# IsoDiffProbe.net
KiCad netlist of a schematic drawn in Altium Designer
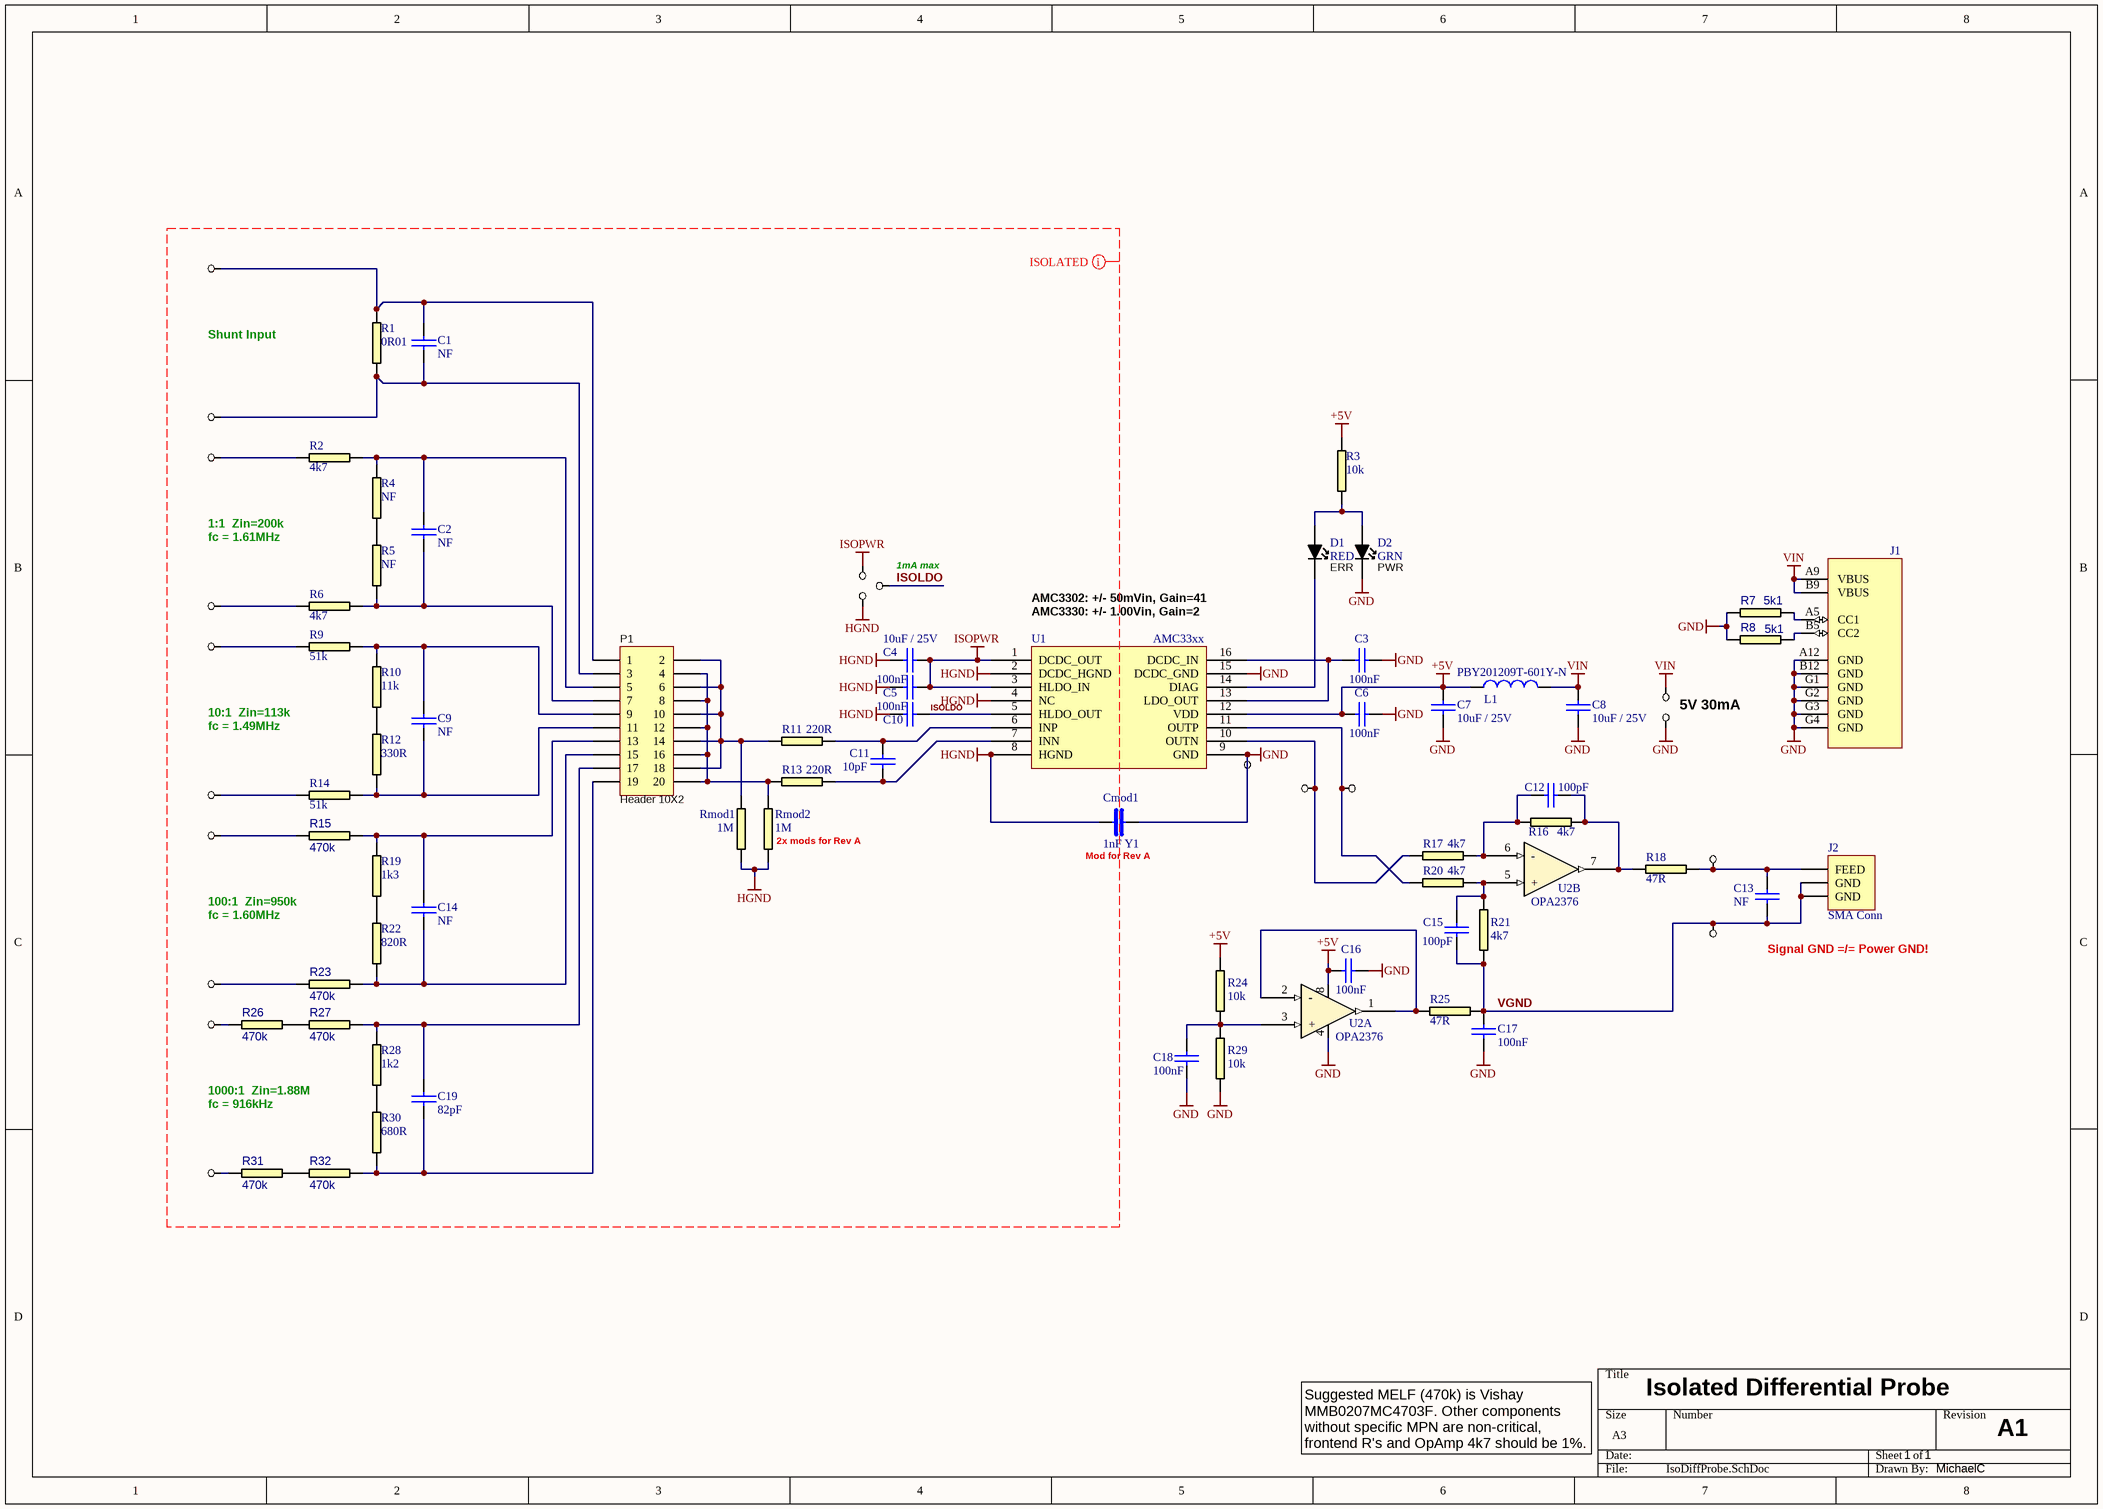
[diagram p0: IsoDiffProbe.SchDoc]

(export (version "E")
  (design (tool "Eeschema 10.0.6"))
  (components
    (comp (ref "C1")
      (value "NF")
      (footprint "NixieClock_RevA:0603")
      (description "Capacitor - S/M")
      (libsource (lib "altium-import") (part "root_0_CAP-STD-SM_"))
    )
    (comp (ref "C2")
      (value "NF")
      (footprint "NixieClock_RevA:0603")
      (description "Capacitor - S/M")
      (libsource (lib "altium-import") (part "root_0_CAP-STD-SM_"))
    )
    (comp (ref "C3")
      (value "100nF")
      (footprint "NixieClock_RevA:0603")
      (description "Capacitor - S/M")
      (libsource (lib "altium-import") (part "root_1_mirrored_CAP-STD-SM_"))
    )
    (comp (ref "C4")
      (value "10uF / 25V")
      (footprint "0805_cap_Rounded")
      (description "Capacitor - S/M")
      (libsource (lib "altium-import") (part "root_1_CAP-STD-SM_"))
    )
    (comp (ref "C5")
      (value "100nF")
      (footprint "NixieClock_RevA:0603")
      (description "Capacitor - S/M")
      (libsource (lib "altium-import") (part "root_1_mirrored_CAP-STD-SM_"))
    )
    (comp (ref "C6")
      (value "100nF")
      (footprint "NixieClock_RevA:0603")
      (description "Capacitor - S/M")
      (libsource (lib "altium-import") (part "root_1_mirrored_CAP-STD-SM_"))
    )
    (comp (ref "C7")
      (value "10uF / 25V")
      (footprint "0805_cap_Rounded")
      (description "Capacitor - S/M")
      (libsource (lib "altium-import") (part "root_0_CAP-STD-SM_"))
    )
    (comp (ref "C8")
      (value "10uF / 25V")
      (footprint "0805_cap_Rounded")
      (description "Capacitor - S/M")
      (libsource (lib "altium-import") (part "root_0_CAP-STD-SM_"))
    )
    (comp (ref "C9")
      (value "NF")
      (footprint "NixieClock_RevA:0603")
      (description "Capacitor - S/M")
      (libsource (lib "altium-import") (part "root_0_CAP-STD-SM_"))
    )
    (comp (ref "C10")
      (value "100nF")
      (footprint "NixieClock_RevA:0603")
      (description "Capacitor - S/M")
      (libsource (lib "altium-import") (part "root_1_mirrored_CAP-STD-SM_"))
    )
    (comp (ref "C11")
      (value "10pF")
      (footprint "NixieClock_RevA:0603")
      (description "Capacitor - S/M")
      (libsource (lib "altium-import") (part "root_0_mirrored_CAP-STD-SM_"))
    )
    (comp (ref "C12")
      (value "100pF")
      (footprint "NixieClock_RevA:0603")
      (description "Capacitor - S/M")
      (libsource (lib "altium-import") (part "root_3_mirrored_CAP-STD-SM_"))
    )
    (comp (ref "C13")
      (value "NF")
      (footprint "NixieClock_RevA:0603")
      (description "Capacitor - S/M")
      (libsource (lib "altium-import") (part "root_0_mirrored_CAP-STD-SM_"))
    )
    (comp (ref "C14")
      (value "NF")
      (footprint "NixieClock_RevA:0603")
      (description "Capacitor - S/M")
      (libsource (lib "altium-import") (part "root_0_CAP-STD-SM_"))
    )
    (comp (ref "C15")
      (value "100pF")
      (footprint "NixieClock_RevA:0603")
      (description "Capacitor - S/M")
      (libsource (lib "altium-import") (part "root_0_mirrored_CAP-STD-SM_"))
    )
    (comp (ref "C16")
      (value "100nF")
      (footprint "NixieClock_RevA:0603")
      (description "Capacitor - S/M")
      (libsource (lib "altium-import") (part "root_3_mirrored_CAP-STD-SM_"))
    )
    (comp (ref "C17")
      (value "100nF")
      (footprint "NixieClock_RevA:0603")
      (description "Capacitor - S/M")
      (libsource (lib "altium-import") (part "root_0_mirrored_CAP-STD-SM_"))
    )
    (comp (ref "C18")
      (value "100nF")
      (footprint "NixieClock_RevA:0603")
      (description "Capacitor - S/M")
      (libsource (lib "altium-import") (part "root_0_mirrored_CAP-STD-SM_"))
    )
    (comp (ref "C19")
      (value "82pF")
      (footprint "NixieClock_RevA:0603")
      (description "Capacitor - S/M")
      (libsource (lib "altium-import") (part "root_0_CAP-STD-SM_"))
    )
    (comp (ref "Cmod1")
      (value "1nF Y1")
      (footprint "RAD0.4Y1")
      (description "Capacitor - Through Hole")
      (libsource (lib "E") (part "CAP-STD-TH"))
    )
    (comp (ref "D1") (value "RED") (footprint "LED-0603") (libsource (lib "NixieClock_RevA") (part "LED")))
    (comp (ref "D2") (value "GRN") (footprint "LED-0603") (libsource (lib "NixieClock_RevA") (part "LED")))
    (comp (ref "J1")
      (value "USB C 6-Pin")
      (footprint "USB-C_6pin_Conn")
      (description "USB Type C Receptacle Power Only (6 pin)")
      (libsource (lib "NixieClock_RevA") (part "USB-C_6pin"))
    )
    (comp (ref "J2")
      (value "SMA Conn")
      (footprint "SMA_SMD")
      (description "SMA connector, mid-mount")
      (libsource (lib "NixieClock_RevA") (part "SMA_SMD"))
    )
    (comp (ref "L1")
      (value "PBY201209T-601Y-N")
      (footprint "0805_Rounded")
      (description "Ferrite Bead WE-CBF, Z = 600 Ohm")
      (libsource (lib "DataloggingClock") (part "PBY201209T-601Y-N"))
    )
    (comp (ref "P1")
      (value "Header 10X2")
      (footprint "IDC20")
      (description "Header, 10-Pin, Dual row")
      (libsource (lib "E") (part "Header 10X2"))
    )
    (comp (ref "R1")
      (value "0R01")
      (footprint "NixieClock_RevA:1206")
      (description "Resistor - S/M")
      (libsource (lib "") (part "RES-SM_2"))
    )
    (comp (ref "R2")
      (value "4k7")
      (footprint "NixieClock_RevA:1206")
      (description "Resistor - S/M")
      (libsource (lib "") (part "RES-SM_3"))
    )
    (comp (ref "R3")
      (value "10k")
      (footprint "NixieClock_RevA:0603")
      (description "Resistor - S/M")
      (libsource (lib "") (part "RES-SM_2"))
    )
    (comp (ref "R4")
      (value "NF")
      (footprint "NixieClock_RevA:0603")
      (description "Resistor - S/M")
      (libsource (lib "") (part "RES-SM_1"))
    )
    (comp (ref "R5")
      (value "NF")
      (footprint "NixieClock_RevA:0603")
      (description "Resistor - S/M")
      (libsource (lib "") (part "RES-SM_1"))
    )
    (comp (ref "R6")
      (value "4k7")
      (footprint "NixieClock_RevA:1206")
      (description "Resistor - S/M")
      (libsource (lib "") (part "RES-SM_3"))
    )
    (comp (ref "R7")
      (value "5k1")
      (footprint "NixieClock_RevA:0603")
      (description "Resistor SMD")
      (libsource (lib "Genesis_SCH_Symbols") (part "ResSMD"))
    )
    (comp (ref "R8")
      (value "5k1")
      (footprint "NixieClock_RevA:0603")
      (description "Resistor SMD")
      (libsource (lib "Genesis_SCH_Symbols") (part "ResSMD"))
    )
    (comp (ref "R9")
      (value "51k")
      (footprint "NixieClock_RevA:1206")
      (description "Resistor - S/M")
      (libsource (lib "") (part "RES-SM_3"))
    )
    (comp (ref "R10")
      (value "11k")
      (footprint "NixieClock_RevA:0603")
      (description "Resistor - S/M")
      (libsource (lib "") (part "RES-SM_1"))
    )
    (comp (ref "R11")
      (value "220R")
      (footprint "NixieClock_RevA:0603")
      (description "Resistor - S/M")
      (libsource (lib "NixieClock_RevA") (part "RES-SM"))
    )
    (comp (ref "R12")
      (value "330R")
      (footprint "NixieClock_RevA:0603")
      (description "Resistor - S/M")
      (libsource (lib "") (part "RES-SM_1"))
    )
    (comp (ref "R13")
      (value "220R")
      (footprint "NixieClock_RevA:0603")
      (description "Resistor - S/M")
      (libsource (lib "NixieClock_RevA") (part "RES-SM"))
    )
    (comp (ref "R14")
      (value "51k")
      (footprint "NixieClock_RevA:1206")
      (description "Resistor - S/M")
      (libsource (lib "") (part "RES-SM_3"))
    )
    (comp (ref "R15")
      (value "470k")
      (footprint "E General:MMB0207")
      (description "Resistor SMD")
      (libsource (lib "NixieClock_RevA") (part "ResSMD"))
    )
    (comp (ref "R16")
      (value "4k7")
      (footprint "NixieClock_RevA:0603")
      (description "Resistor - S/M")
      (libsource (lib "") (part "RES-SM_3"))
    )
    (comp (ref "R17")
      (value "4k7")
      (footprint "NixieClock_RevA:0603")
      (description "Resistor - S/M")
      (libsource (lib "NixieClock_RevA") (part "RES-SM"))
    )
    (comp (ref "R18")
      (value "47R")
      (footprint "NixieClock_RevA:0603")
      (description "Resistor - S/M")
      (libsource (lib "NixieClock_RevA") (part "RES-SM"))
    )
    (comp (ref "R19")
      (value "1k3")
      (footprint "NixieClock_RevA:0603")
      (description "Resistor - S/M")
      (libsource (lib "") (part "RES-SM_1"))
    )
    (comp (ref "R20")
      (value "4k7")
      (footprint "NixieClock_RevA:0603")
      (description "Resistor - S/M")
      (libsource (lib "NixieClock_RevA") (part "RES-SM"))
    )
    (comp (ref "R21")
      (value "4k7")
      (footprint "NixieClock_RevA:0603")
      (description "Resistor - S/M")
      (libsource (lib "") (part "RES-SM_1"))
    )
    (comp (ref "R22")
      (value "820R")
      (footprint "NixieClock_RevA:0603")
      (description "Resistor - S/M")
      (libsource (lib "") (part "RES-SM_1"))
    )
    (comp (ref "R23")
      (value "470k")
      (footprint "E General:MMB0207")
      (description "Resistor SMD")
      (libsource (lib "NixieClock_RevA") (part "ResSMD"))
    )
    (comp (ref "R24")
      (value "10k")
      (footprint "NixieClock_RevA:0603")
      (description "Resistor - S/M")
      (libsource (lib "") (part "RES-SM_1"))
    )
    (comp (ref "R25")
      (value "47R")
      (footprint "NixieClock_RevA:0603")
      (description "Resistor - S/M")
      (libsource (lib "NixieClock_RevA") (part "RES-SM"))
    )
    (comp (ref "R26")
      (value "470k")
      (footprint "E General:MMB0207")
      (description "Resistor SMD")
      (libsource (lib "NixieClock_RevA") (part "ResSMD"))
    )
    (comp (ref "R27")
      (value "470k")
      (footprint "E General:MMB0207")
      (description "Resistor SMD")
      (libsource (lib "NixieClock_RevA") (part "ResSMD"))
    )
    (comp (ref "R28")
      (value "1k2")
      (footprint "NixieClock_RevA:0603")
      (description "Resistor - S/M")
      (libsource (lib "") (part "RES-SM_1"))
    )
    (comp (ref "R29")
      (value "10k")
      (footprint "NixieClock_RevA:0603")
      (description "Resistor - S/M")
      (libsource (lib "") (part "RES-SM_1"))
    )
    (comp (ref "R30")
      (value "680R")
      (footprint "NixieClock_RevA:0603")
      (description "Resistor - S/M")
      (libsource (lib "") (part "RES-SM_1"))
    )
    (comp (ref "R31")
      (value "470k")
      (footprint "E General:MMB0207")
      (description "Resistor SMD")
      (libsource (lib "NixieClock_RevA") (part "ResSMD"))
    )
    (comp (ref "R32")
      (value "470k")
      (footprint "E General:MMB0207")
      (description "Resistor SMD")
      (libsource (lib "NixieClock_RevA") (part "ResSMD"))
    )
    (comp (ref "Rmod1")
      (value "1M")
      (footprint "NixieClock_RevA:0603")
      (description "Resistor - S/M")
      (libsource (lib "") (part "RES-SM_1"))
    )
    (comp (ref "Rmod2")
      (value "1M")
      (footprint "NixieClock_RevA:0603")
      (description "Resistor - S/M")
      (libsource (lib "") (part "RES-SM_1"))
    )
    (comp (ref "TP1")
      (value "Test Point")
      (footprint "TP")
      (description "Pad for Test Point")
      (libsource (lib "E") (part "TP"))
    )
    (comp (ref "TP2")
      (value "Test Point")
      (footprint "TP")
      (description "Pad for Test Point")
      (libsource (lib "E") (part "TP"))
    )
    (comp (ref "TP3")
      (value "Test Point")
      (footprint "TP")
      (description "Pad for Test Point")
      (libsource (lib "E") (part "TP"))
    )
    (comp (ref "TP4")
      (value "Test Point")
      (footprint "TP")
      (description "Pad for Test Point")
      (libsource (lib "E") (part "TP"))
    )
    (comp (ref "TP5")
      (value "Test Point")
      (footprint "TP")
      (description "Pad for Test Point")
      (libsource (lib "E") (part "TP"))
    )
    (comp (ref "TP6")
      (value "Test Point")
      (footprint "TP")
      (description "Pad for Test Point")
      (libsource (lib "E") (part "TP"))
    )
    (comp (ref "TP7")
      (value "Test Point")
      (footprint "TP")
      (description "Pad for Test Point")
      (libsource (lib "E") (part "TP"))
    )
    (comp (ref "TP8")
      (value "Test Point")
      (footprint "TP")
      (description "Pad for Test Point")
      (libsource (lib "E") (part "TP"))
    )
    (comp (ref "TP9")
      (value "Test Point")
      (footprint "TP")
      (description "Pad for Test Point")
      (libsource (lib "E") (part "TP"))
    )
    (comp (ref "TP10")
      (value "Test Point")
      (footprint "TP")
      (description "Pad for Test Point")
      (libsource (lib "E") (part "TP"))
    )
    (comp (ref "TP11")
      (value "Test Point")
      (footprint "TP")
      (description "Pad for Test Point")
      (libsource (lib "E") (part "TP"))
    )
    (comp (ref "TP12")
      (value "Test Point")
      (footprint "TP")
      (description "Pad for Test Point")
      (libsource (lib "E") (part "TP"))
    )
    (comp (ref "TP13")
      (value "Test Point")
      (footprint "TP")
      (description "Pad for Test Point")
      (libsource (lib "E") (part "TP"))
    )
    (comp (ref "TP14")
      (value "Test Point")
      (footprint "TP")
      (description "Pad for Test Point")
      (libsource (lib "E") (part "TP"))
    )
    (comp (ref "TP15")
      (value "Test Point")
      (footprint "TP")
      (description "Pad for Test Point")
      (libsource (lib "E") (part "TP"))
    )
    (comp (ref "TP16")
      (value "Test Point")
      (footprint "TP")
      (description "Pad for Test Point")
      (libsource (lib "E") (part "TP"))
    )
    (comp (ref "TP17")
      (value "Test Point")
      (footprint "TP")
      (description "Pad for Test Point")
      (libsource (lib "E") (part "TP"))
    )
    (comp (ref "TP18")
      (value "Test Point")
      (footprint "TP")
      (description "Pad for Test Point")
      (libsource (lib "E") (part "TP"))
    )
    (comp (ref "TP19")
      (value "Test Point")
      (footprint "TP")
      (description "Pad for Test Point")
      (libsource (lib "E") (part "TP"))
    )
    (comp (ref "TP20")
      (value "Test Point")
      (footprint "TP")
      (description "Pad for Test Point")
      (libsource (lib "E") (part "TP"))
    )
    (comp (ref "U1")
      (value "AMC33xx")
      (footprint "DW0016B")
      (description "Isolated differential analog sensor")
      (libsource (lib "NixieClock_RevA") (part "AMC330X"))
    )
    (comp (ref "U2")
      (value "OPA2376")
      (footprint "SO-8")
      (description "PRECISION DUAL OPERATIONAL AMPLIFIER")
      (libsource (lib "") (part "TLC272ID_1"))
    )
  )
  (nets
    (net (code "1") (name "+5V") (class "Default")
      (node (ref "C16") (pin "1") (pintype "passive"))
      (node (ref "C6") (pin "2") (pintype "passive"))
      (node (ref "C7") (pin "1") (pintype "passive"))
      (node (ref "L1") (pin "1") (pinfunction "1_1") (pintype "passive"))
      (node (ref "R24") (pin "1") (pintype "passive"))
      (node (ref "R3") (pin "2") (pintype "passive"))
      (node (ref "U1") (pin "12") (pinfunction "VDD_12") (pintype "passive"))
      (node (ref "U2") (pin "8") (pinfunction "VDD_8") (pintype "power_in"))
    )
    (net (code "2") (name "/ISOLDO") (class "Default")
      (node (ref "C10") (pin "1") (pintype "passive"))
      (node (ref "TP20") (pin "1") (pinfunction "0_1") (pintype "passive"))
      (node (ref "U1") (pin "5") (pinfunction "HLDO_OUT_5") (pintype "passive"))
    )
    (net (code "3") (name "/VGND") (class "Default")
      (node (ref "C13") (pin "2") (pintype "passive"))
      (node (ref "C15") (pin "2") (pintype "passive"))
      (node (ref "C17") (pin "1") (pintype "passive"))
      (node (ref "J2") (pin "GND") (pinfunction "GND_GND") (pintype "passive"))
      (node (ref "R21") (pin "2") (pintype "passive"))
      (node (ref "R25") (pin "1") (pintype "passive"))
      (node (ref "TP16") (pin "1") (pinfunction "0_1") (pintype "passive"))
    )
    (net (code "4") (name "GND") (class "Default")
      (node (ref "C16") (pin "2") (pintype "passive"))
      (node (ref "C17") (pin "2") (pintype "passive"))
      (node (ref "C18") (pin "2") (pintype "passive"))
      (node (ref "C3") (pin "1") (pintype "passive"))
      (node (ref "C6") (pin "1") (pintype "passive"))
      (node (ref "C7") (pin "2") (pintype "passive"))
      (node (ref "C8") (pin "2") (pintype "passive"))
      (node (ref "Cmod1") (pin "2") (pintype "passive"))
      (node (ref "D2") (pin "K") (pintype "passive"))
      (node (ref "J1") (pin "A12") (pinfunction "GND_A12") (pintype "power_in"))
      (node (ref "J1") (pin "B12") (pinfunction "GND_B12") (pintype "power_in"))
      (node (ref "J1") (pin "G1") (pinfunction "GND_G1") (pintype "power_in"))
      (node (ref "J1") (pin "G2") (pinfunction "GND_G2") (pintype "power_in"))
      (node (ref "J1") (pin "G3") (pinfunction "GND_G3") (pintype "power_in"))
      (node (ref "J1") (pin "G4") (pinfunction "GND_G4") (pintype "power_in"))
      (node (ref "R29") (pin "2") (pintype "passive"))
      (node (ref "R7") (pin "1") (pintype "passive"))
      (node (ref "R8") (pin "1") (pintype "passive"))
      (node (ref "TP19") (pin "1") (pinfunction "0_1") (pintype "passive"))
      (node (ref "TP7") (pin "1") (pinfunction "0_1") (pintype "passive"))
      (node (ref "U1") (pin "15") (pinfunction "DCDC_GND_15") (pintype "passive"))
      (node (ref "U1") (pin "9") (pinfunction "GND_9") (pintype "passive"))
      (node (ref "U2") (pin "4") (pinfunction "GND_4") (pintype "power_in"))
    )
    (net (code "5") (name "HGND") (class "Default")
      (node (ref "C10") (pin "2") (pintype "passive"))
      (node (ref "C4") (pin "1") (pintype "passive"))
      (node (ref "C5") (pin "2") (pintype "passive"))
      (node (ref "Cmod1") (pin "1") (pintype "passive"))
      (node (ref "Rmod1") (pin "2") (pintype "passive"))
      (node (ref "Rmod2") (pin "2") (pintype "passive"))
      (node (ref "TP18") (pin "1") (pinfunction "0_1") (pintype "passive"))
      (node (ref "U1") (pin "2") (pinfunction "DCDC_HGND_2") (pintype "passive"))
      (node (ref "U1") (pin "4") (pinfunction "NC_4") (pintype "passive"))
      (node (ref "U1") (pin "8") (pinfunction "HGND_8") (pintype "passive"))
    )
    (net (code "6") (name "ISOPWR") (class "Default")
      (node (ref "C4") (pin "2") (pintype "passive"))
      (node (ref "C5") (pin "1") (pintype "passive"))
      (node (ref "TP17") (pin "1") (pinfunction "0_1") (pintype "passive"))
      (node (ref "U1") (pin "1") (pinfunction "DCDC_OUT_1") (pintype "passive"))
      (node (ref "U1") (pin "3") (pinfunction "HLDO_IN_3") (pintype "passive"))
    )
    (net (code "7") (name "Net-(C2-Pad1)") (class "Default")
      (node (ref "C2") (pin "1") (pintype "passive"))
      (node (ref "P1") (pin "5") (pinfunction "5_5") (pintype "passive"))
      (node (ref "R2") (pin "2") (pintype "passive"))
      (node (ref "R4") (pin "1") (pintype "passive"))
    )
    (net (code "8") (name "Net-(C2-Pad2)") (class "Default")
      (node (ref "C2") (pin "2") (pintype "passive"))
      (node (ref "P1") (pin "7") (pinfunction "7_7") (pintype "passive"))
      (node (ref "R5") (pin "2") (pintype "passive"))
      (node (ref "R6") (pin "2") (pintype "passive"))
    )
    (net (code "9") (name "Net-(C9-Pad1)") (class "Default")
      (node (ref "C9") (pin "1") (pintype "passive"))
      (node (ref "P1") (pin "9") (pinfunction "9_9") (pintype "passive"))
      (node (ref "R10") (pin "1") (pintype "passive"))
      (node (ref "R9") (pin "2") (pintype "passive"))
    )
    (net (code "10") (name "Net-(C9-Pad2)") (class "Default")
      (node (ref "C9") (pin "2") (pintype "passive"))
      (node (ref "P1") (pin "11") (pinfunction "11_11") (pintype "passive"))
      (node (ref "R12") (pin "2") (pintype "passive"))
      (node (ref "R14") (pin "2") (pintype "passive"))
    )
    (net (code "11") (name "Net-(C14-Pad1)") (class "Default")
      (node (ref "C14") (pin "1") (pintype "passive"))
      (node (ref "P1") (pin "13") (pinfunction "13_13") (pintype "passive"))
      (node (ref "R15") (pin "2") (pintype "passive"))
      (node (ref "R19") (pin "1") (pintype "passive"))
    )
    (net (code "12") (name "Net-(C14-Pad2)") (class "Default")
      (node (ref "C14") (pin "2") (pintype "passive"))
      (node (ref "P1") (pin "15") (pinfunction "15_15") (pintype "passive"))
      (node (ref "R22") (pin "2") (pintype "passive"))
      (node (ref "R23") (pin "2") (pintype "passive"))
    )
    (net (code "13") (name "Net-(C19-Pad1)") (class "Default")
      (node (ref "C19") (pin "1") (pintype "passive"))
      (node (ref "P1") (pin "17") (pinfunction "17_17") (pintype "passive"))
      (node (ref "R27") (pin "2") (pintype "passive"))
      (node (ref "R28") (pin "1") (pintype "passive"))
    )
    (net (code "14") (name "Net-(C19-Pad2)") (class "Default")
      (node (ref "C19") (pin "2") (pintype "passive"))
      (node (ref "P1") (pin "19") (pinfunction "19_19") (pintype "passive"))
      (node (ref "R30") (pin "2") (pintype "passive"))
      (node (ref "R32") (pin "2") (pintype "passive"))
    )
    (net (code "15") (name "Net-(D1-PadA)") (class "Default")
      (node (ref "D1") (pin "A") (pintype "passive"))
      (node (ref "D2") (pin "A") (pintype "passive"))
      (node (ref "R3") (pin "1") (pintype "passive"))
    )
    (net (code "16") (name "Net-(J1-CC1)") (class "Default")
      (node (ref "J1") (pin "A5") (pinfunction "CC1_A5") (pintype "bidirectional"))
      (node (ref "R7") (pin "2") (pintype "passive"))
    )
    (net (code "17") (name "Net-(J1-CC2)") (class "Default")
      (node (ref "J1") (pin "B5") (pinfunction "CC2_B5") (pintype "bidirectional"))
      (node (ref "R8") (pin "2") (pintype "passive"))
    )
    (net (code "18") (name "Net-(P1-Pad10)") (class "Default")
      (node (ref "P1") (pin "10") (pinfunction "10_10") (pintype "passive"))
      (node (ref "P1") (pin "14") (pinfunction "14_14") (pintype "passive"))
      (node (ref "P1") (pin "18") (pinfunction "18_18") (pintype "passive"))
      (node (ref "P1") (pin "2") (pinfunction "2_2") (pintype "passive"))
      (node (ref "P1") (pin "6") (pinfunction "6_6") (pintype "passive"))
      (node (ref "R11") (pin "2") (pintype "passive"))
      (node (ref "Rmod1") (pin "1") (pintype "passive"))
    )
    (net (code "19") (name "Net-(P1-Pad12)") (class "Default")
      (node (ref "P1") (pin "12") (pinfunction "12_12") (pintype "passive"))
      (node (ref "P1") (pin "16") (pinfunction "16_16") (pintype "passive"))
      (node (ref "P1") (pin "20") (pinfunction "20_20") (pintype "passive"))
      (node (ref "P1") (pin "4") (pinfunction "4_4") (pintype "passive"))
      (node (ref "P1") (pin "8") (pinfunction "8_8") (pintype "passive"))
      (node (ref "R13") (pin "2") (pintype "passive"))
      (node (ref "Rmod2") (pin "1") (pintype "passive"))
    )
    (net (code "20") (name "Net-(R4-Pad2)") (class "Default")
      (node (ref "R4") (pin "2") (pintype "passive"))
      (node (ref "R5") (pin "1") (pintype "passive"))
    )
    (net (code "21") (name "Net-(R10-Pad2)") (class "Default")
      (node (ref "R10") (pin "2") (pintype "passive"))
      (node (ref "R12") (pin "1") (pintype "passive"))
    )
    (net (code "22") (name "Net-(R19-Pad2)") (class "Default")
      (node (ref "R19") (pin "2") (pintype "passive"))
      (node (ref "R22") (pin "1") (pintype "passive"))
    )
    (net (code "23") (name "Net-(R26-Pad2)") (class "Default")
      (node (ref "R26") (pin "2") (pintype "passive"))
      (node (ref "R27") (pin "1") (pintype "passive"))
    )
    (net (code "24") (name "Net-(R28-Pad2)") (class "Default")
      (node (ref "R28") (pin "2") (pintype "passive"))
      (node (ref "R30") (pin "1") (pintype "passive"))
    )
    (net (code "25") (name "Net-(R31-Pad2)") (class "Default")
      (node (ref "R31") (pin "2") (pintype "passive"))
      (node (ref "R32") (pin "1") (pintype "passive"))
    )
    (net (code "26") (name "Net-(TP1-0)") (class "Default")
      (node (ref "C1") (pin "1") (pintype "passive"))
      (node (ref "P1") (pin "1") (pinfunction "1_1") (pintype "passive"))
      (node (ref "R1") (pin "2") (pintype "passive"))
      (node (ref "TP1") (pin "1") (pinfunction "0_1") (pintype "passive"))
    )
    (net (code "27") (name "Net-(TP2-0)") (class "Default")
      (node (ref "C1") (pin "2") (pintype "passive"))
      (node (ref "P1") (pin "3") (pinfunction "3_3") (pintype "passive"))
      (node (ref "R1") (pin "1") (pintype "passive"))
      (node (ref "TP2") (pin "1") (pinfunction "0_1") (pintype "passive"))
    )
    (net (code "28") (name "Net-(TP3-0)") (class "Default")
      (node (ref "R2") (pin "1") (pintype "passive"))
      (node (ref "TP3") (pin "1") (pinfunction "0_1") (pintype "passive"))
    )
    (net (code "29") (name "Net-(TP4-0)") (class "Default")
      (node (ref "R6") (pin "1") (pintype "passive"))
      (node (ref "TP4") (pin "1") (pinfunction "0_1") (pintype "passive"))
    )
    (net (code "30") (name "Net-(TP5-0)") (class "Default")
      (node (ref "R9") (pin "1") (pintype "passive"))
      (node (ref "TP5") (pin "1") (pinfunction "0_1") (pintype "passive"))
    )
    (net (code "31") (name "Net-(TP8-0)") (class "Default")
      (node (ref "R14") (pin "1") (pintype "passive"))
      (node (ref "TP8") (pin "1") (pinfunction "0_1") (pintype "passive"))
    )
    (net (code "32") (name "Net-(TP9-0)") (class "Default")
      (node (ref "R15") (pin "1") (pintype "passive"))
      (node (ref "TP9") (pin "1") (pinfunction "0_1") (pintype "passive"))
    )
    (net (code "33") (name "Net-(TP10-0)") (class "Default")
      (node (ref "R23") (pin "1") (pintype "passive"))
      (node (ref "TP10") (pin "1") (pinfunction "0_1") (pintype "passive"))
    )
    (net (code "34") (name "Net-(TP11-0)") (class "Default")
      (node (ref "R26") (pin "1") (pintype "passive"))
      (node (ref "TP11") (pin "1") (pinfunction "0_1") (pintype "passive"))
    )
    (net (code "35") (name "Net-(TP12-0)") (class "Default")
      (node (ref "R31") (pin "1") (pintype "passive"))
      (node (ref "TP12") (pin "1") (pinfunction "0_1") (pintype "passive"))
    )
    (net (code "36") (name "Net-(TP13-0)") (class "Default")
      (node (ref "R17") (pin "2") (pintype "passive"))
      (node (ref "TP13") (pin "1") (pinfunction "0_1") (pintype "passive"))
      (node (ref "U1") (pin "10") (pinfunction "OUTN_10") (pintype "passive"))
    )
    (net (code "37") (name "Net-(TP14-0)") (class "Default")
      (node (ref "R20") (pin "2") (pintype "passive"))
      (node (ref "TP14") (pin "1") (pinfunction "0_1") (pintype "passive"))
      (node (ref "U1") (pin "11") (pinfunction "OUTP_11") (pintype "passive"))
    )
    (net (code "38") (name "Net-(TP15-0)") (class "Default")
      (node (ref "C13") (pin "1") (pintype "passive"))
      (node (ref "J2") (pin "FEED") (pinfunction "FEED_FEED") (pintype "passive"))
      (node (ref "R18") (pin "1") (pintype "passive"))
      (node (ref "TP15") (pin "1") (pinfunction "0_1") (pintype "passive"))
    )
    (net (code "39") (name "Net-(U1-DCDC_IN)") (class "Default")
      (node (ref "C3") (pin "2") (pintype "passive"))
      (node (ref "U1") (pin "13") (pinfunction "LDO_OUT_13") (pintype "passive"))
      (node (ref "U1") (pin "16") (pinfunction "DCDC_IN_16") (pintype "passive"))
    )
    (net (code "40") (name "Net-(U1-DIAG)") (class "Default")
      (node (ref "D1") (pin "K") (pintype "passive"))
      (node (ref "U1") (pin "14") (pinfunction "DIAG_14") (pintype "passive"))
    )
    (net (code "41") (name "Net-(U1-INN)") (class "Default")
      (node (ref "C11") (pin "2") (pintype "passive"))
      (node (ref "R13") (pin "1") (pintype "passive"))
      (node (ref "U1") (pin "7") (pinfunction "INN_7") (pintype "passive"))
    )
    (net (code "42") (name "Net-(U1-INP)") (class "Default")
      (node (ref "C11") (pin "1") (pintype "passive"))
      (node (ref "R11") (pin "1") (pintype "passive"))
      (node (ref "U1") (pin "6") (pinfunction "INP_6") (pintype "passive"))
    )
    (net (code "43") (name "Net-(U2A-+)") (class "Default")
      (node (ref "C18") (pin "1") (pintype "passive"))
      (node (ref "R24") (pin "2") (pintype "passive"))
      (node (ref "R29") (pin "1") (pintype "passive"))
      (node (ref "U2") (pin "3") (pinfunction "+_3") (pintype "input"))
    )
    (net (code "44") (name "Net-(U2A--)") (class "Default")
      (node (ref "R25") (pin "2") (pintype "passive"))
      (node (ref "U2") (pin "1") (pinfunction "1OUT_1") (pintype "output"))
      (node (ref "U2") (pin "2") (pinfunction "-_2") (pintype "input"))
    )
    (net (code "45") (name "Net-(U2B-+)") (class "Default")
      (node (ref "C15") (pin "1") (pintype "passive"))
      (node (ref "R20") (pin "1") (pintype "passive"))
      (node (ref "R21") (pin "1") (pintype "passive"))
      (node (ref "U2") (pin "5") (pinfunction "+_5") (pintype "input"))
    )
    (net (code "46") (name "Net-(U2B--)") (class "Default")
      (node (ref "C12") (pin "1") (pintype "passive"))
      (node (ref "R16") (pin "1") (pintype "passive"))
      (node (ref "R17") (pin "1") (pintype "passive"))
      (node (ref "U2") (pin "6") (pinfunction "-_6") (pintype "input"))
    )
    (net (code "47") (name "Net-(U2B-2OUT)") (class "Default")
      (node (ref "C12") (pin "2") (pintype "passive"))
      (node (ref "R16") (pin "2") (pintype "passive"))
      (node (ref "R18") (pin "2") (pintype "passive"))
      (node (ref "U2") (pin "7") (pinfunction "2OUT_7") (pintype "output"))
    )
    (net (code "48") (name "VIN") (class "Default")
      (node (ref "C8") (pin "1") (pintype "passive"))
      (node (ref "J1") (pin "A9") (pinfunction "VBUS_A9") (pintype "power_in"))
      (node (ref "J1") (pin "B9") (pinfunction "VBUS_B9") (pintype "power_in"))
      (node (ref "L1") (pin "2") (pinfunction "2_2") (pintype "passive"))
      (node (ref "TP6") (pin "1") (pinfunction "0_1") (pintype "passive"))
    )
  )
)
